# Supply.net
KiCad netlist of a schematic drawn in Altium Designer
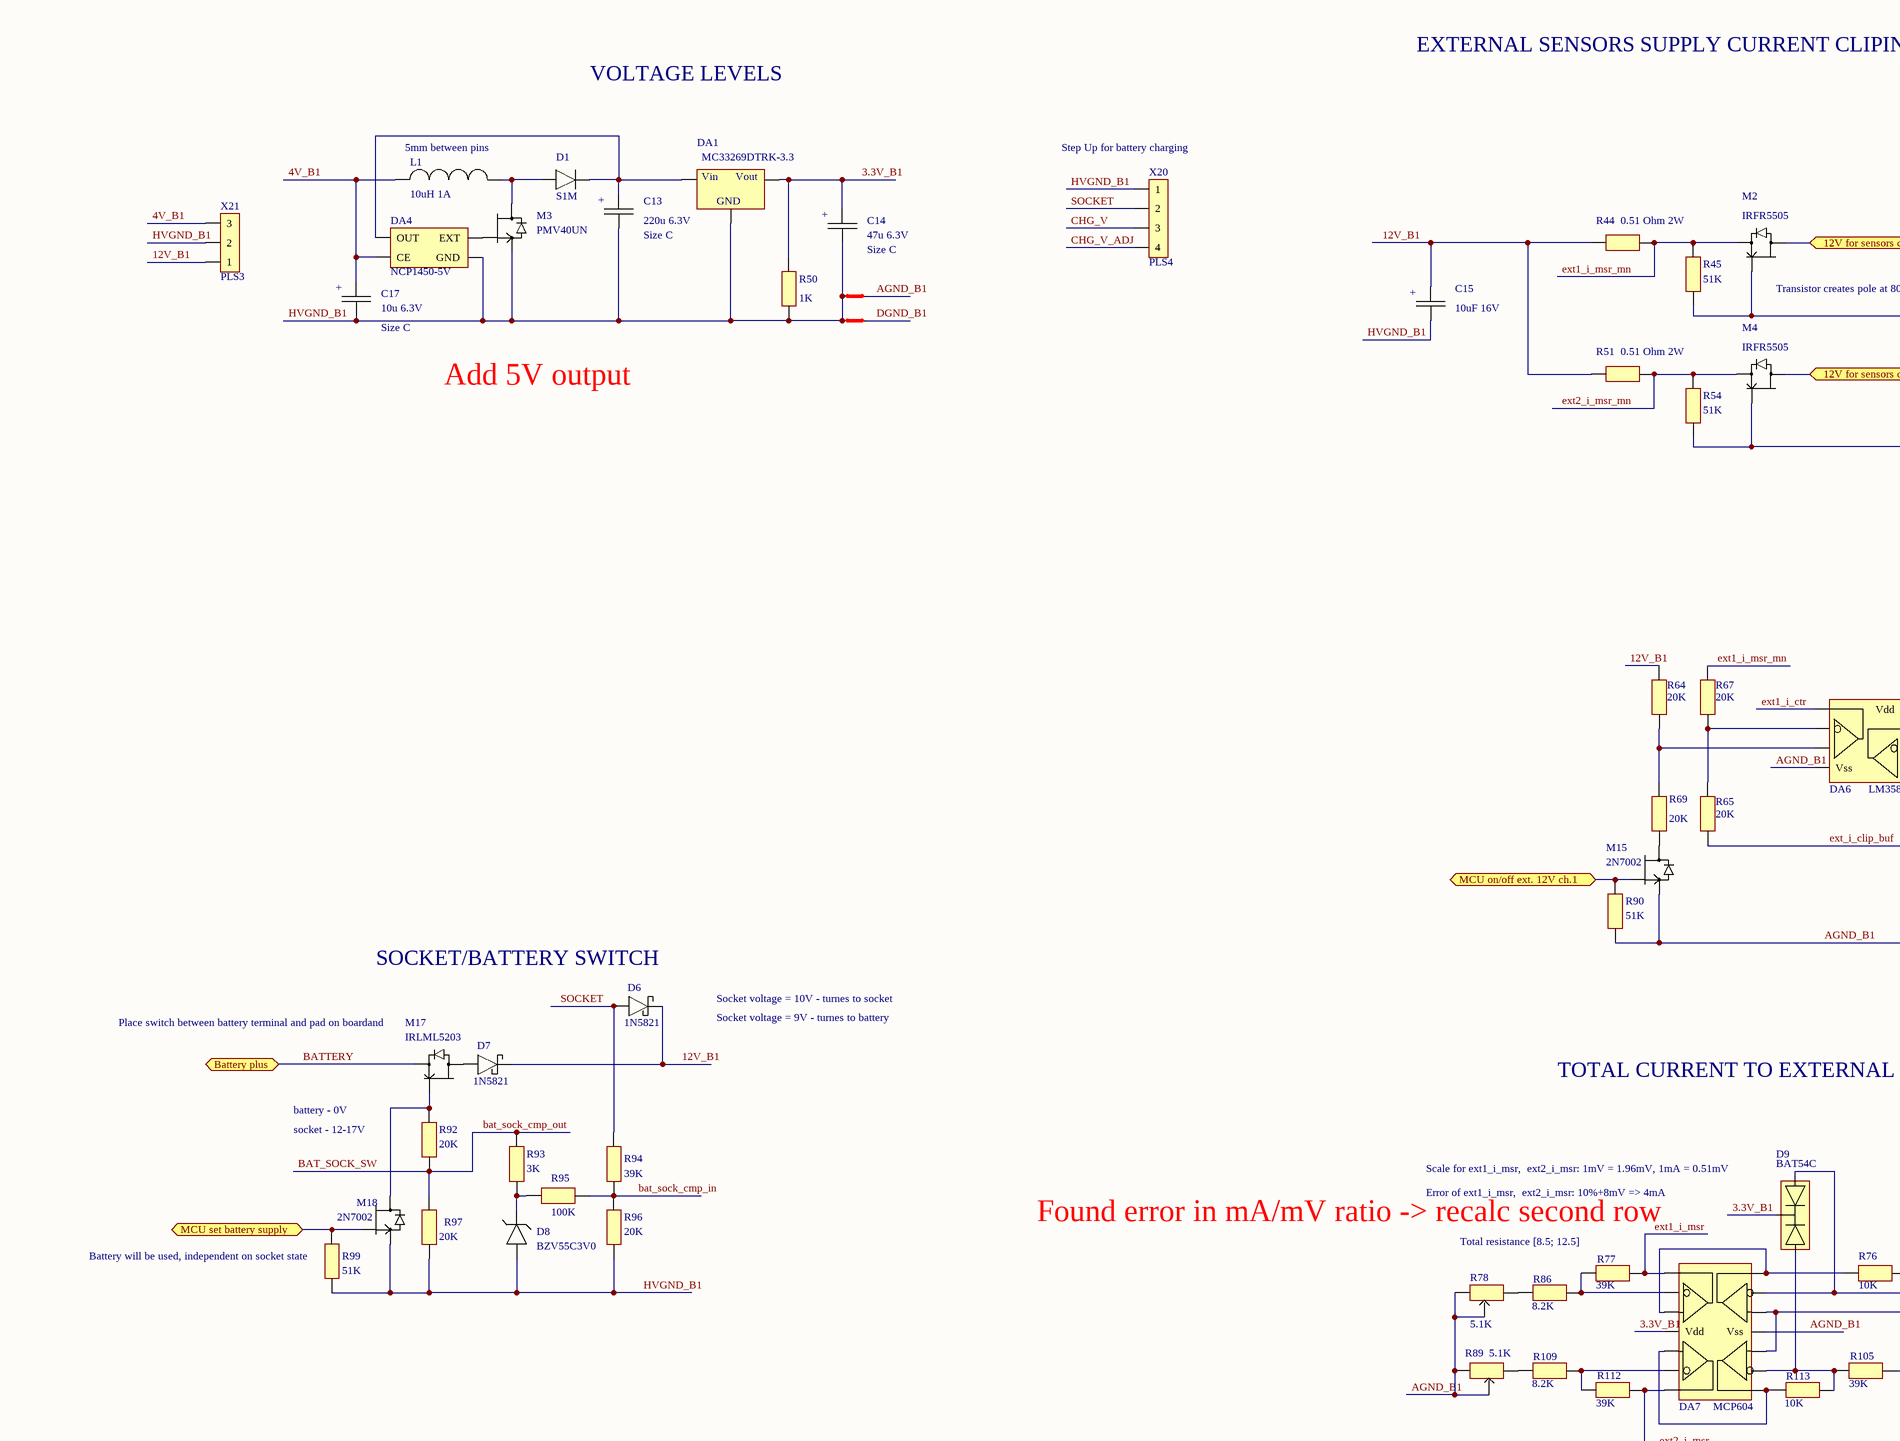
[diagram p0: Supply.SchDoc, top left]
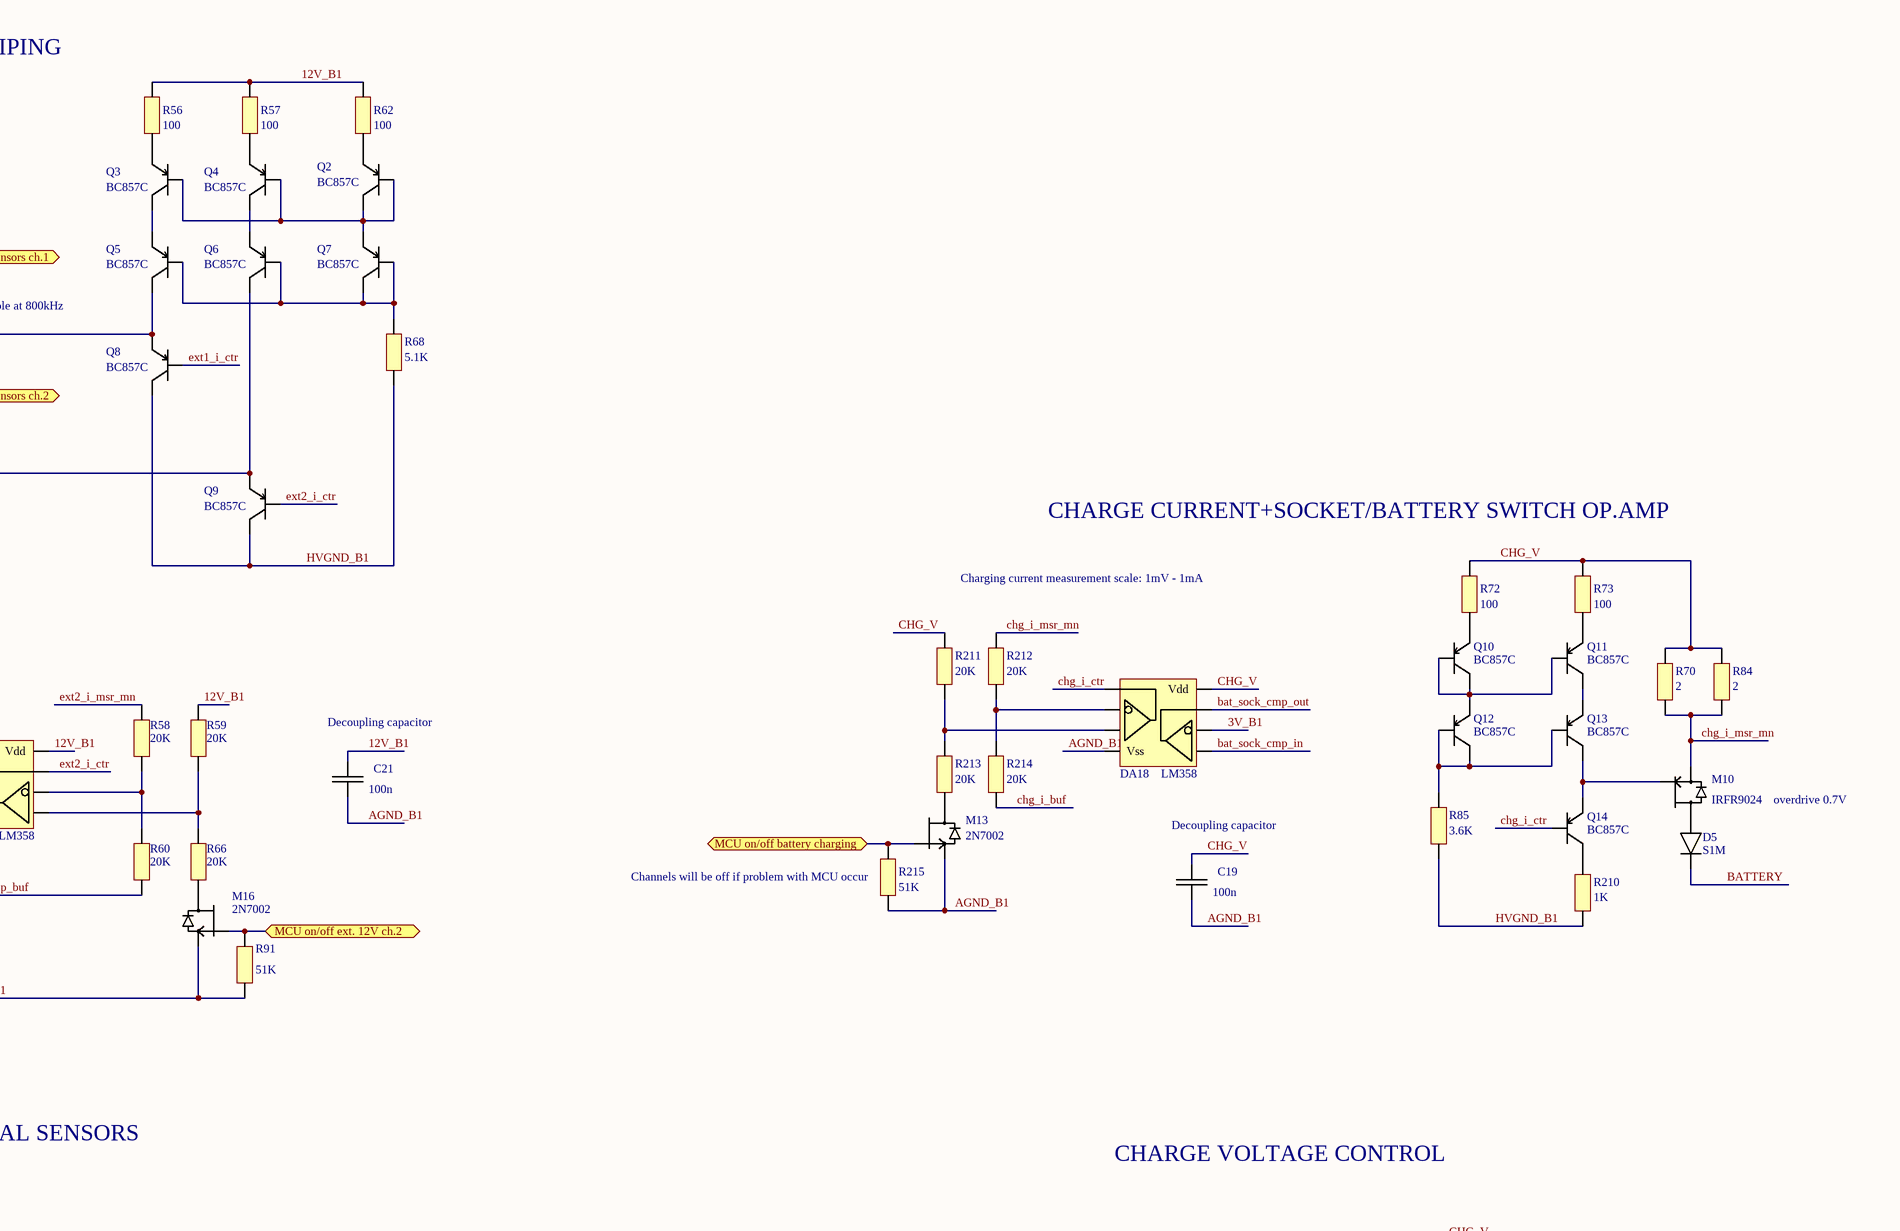
[diagram p1: Supply.SchDoc, top right]
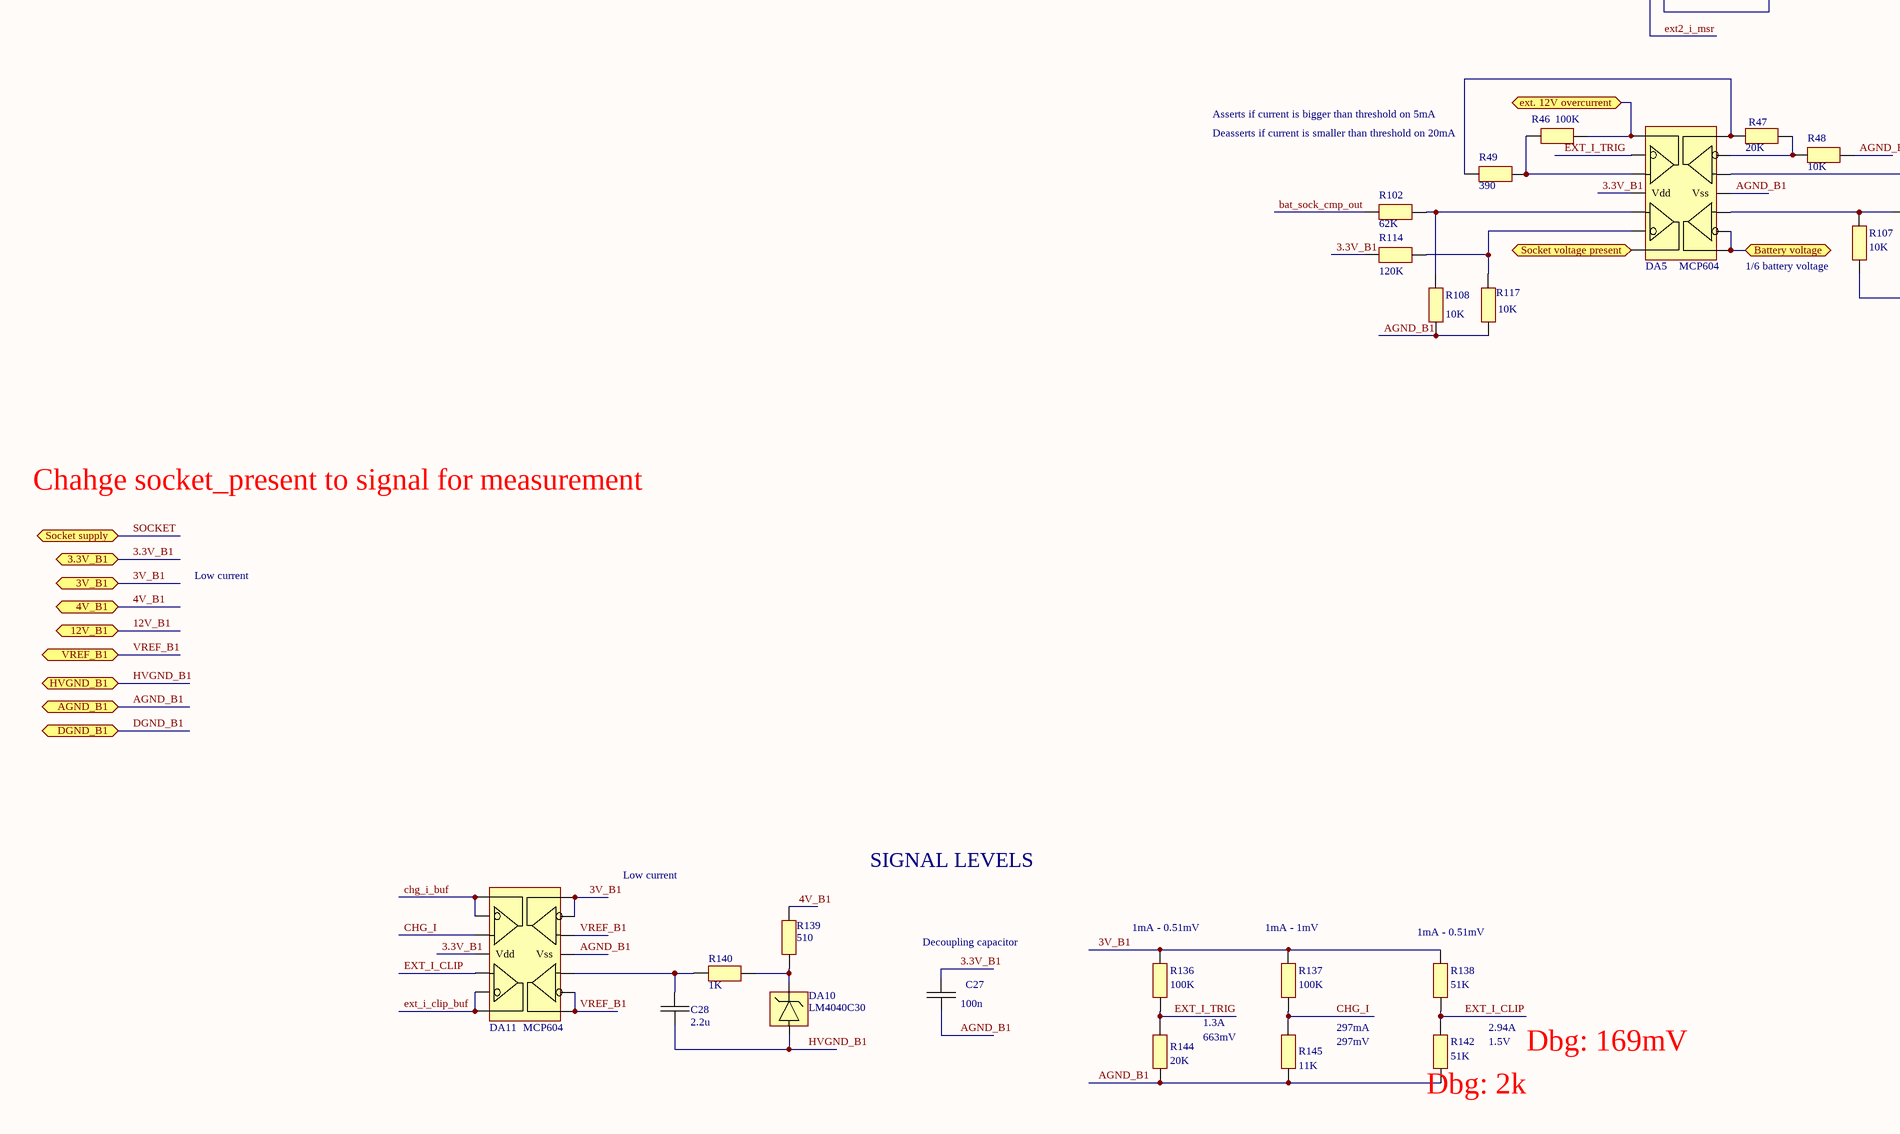
[diagram p2: Supply.SchDoc, bottom left]
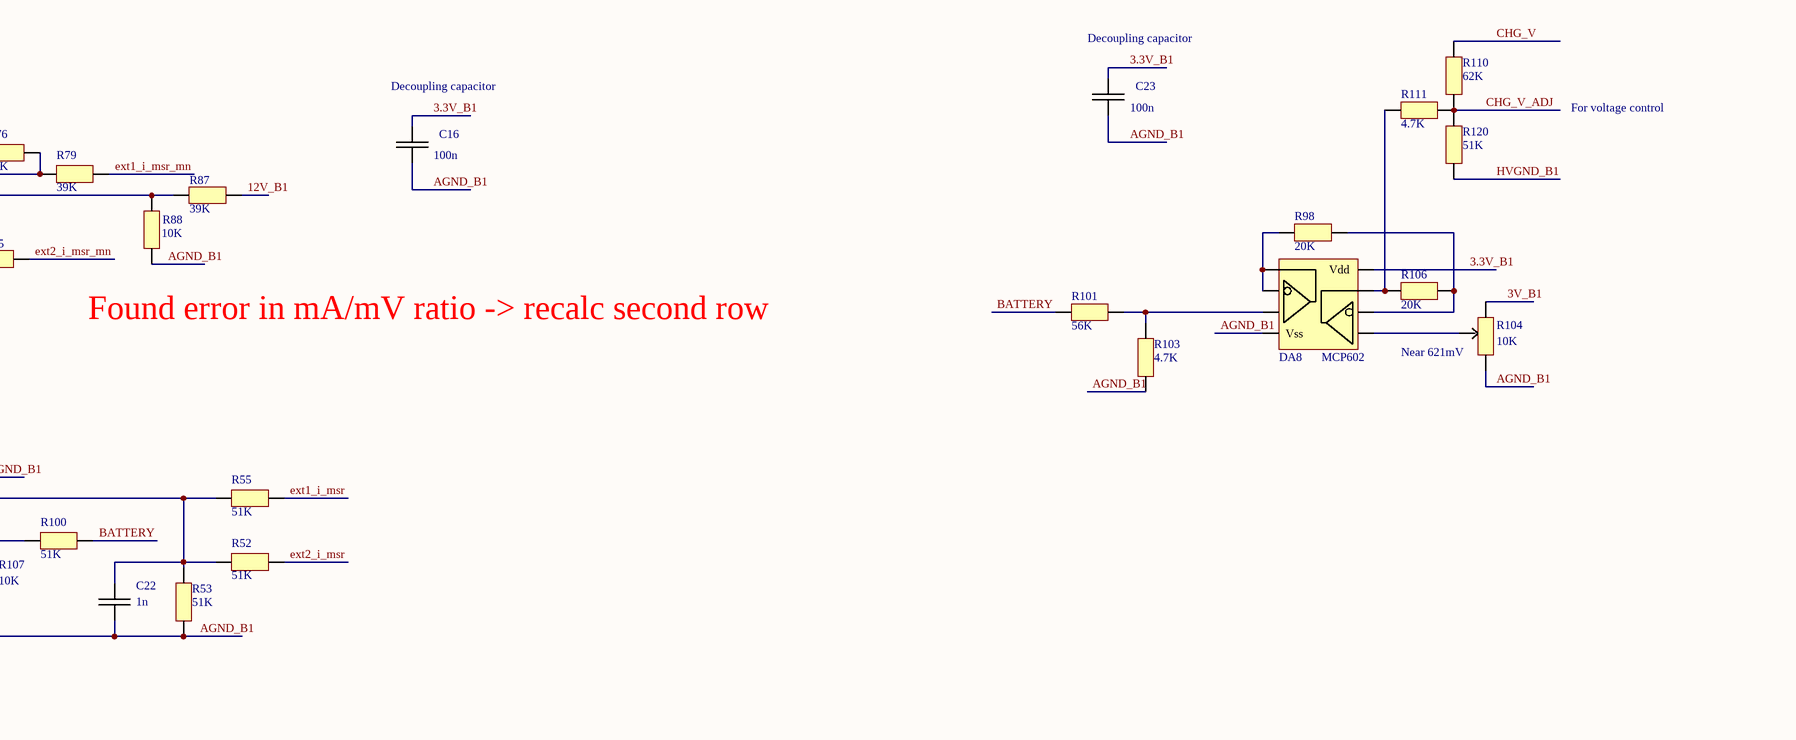
[diagram p3: Supply.SchDoc, bottom right]

(export (version "E")
  (design (tool "Eeschema 10.0.6"))
  (components
    (comp (ref "C13")
      (value "220u 6.3V")
      (footprint "CALUM_SMD_C")
      (libsource (lib "PRIM_fact") (part "C_POL"))
    )
    (comp (ref "C14")
      (value "47u 6.3V")
      (footprint "CALUM_SMD_C")
      (libsource (lib "PRIM_fact") (part "C_POL"))
    )
    (comp (ref "C15")
      (value "10uF 16V")
      (footprint "CALUM_THT_E5D13")
      (libsource (lib "PRIM_fact") (part "C_POL"))
    )
    (comp (ref "C16") (value "100n") (footprint "0805") (libsource (lib "PRIM_fact") (part "C")))
    (comp (ref "C17")
      (value "10u 6.3V")
      (footprint "CALUM_SMD_C")
      (libsource (lib "PRIM_fact") (part "C_POL"))
    )
    (comp (ref "C19") (value "100n") (footprint "0805") (libsource (lib "PRIM_fact") (part "C")))
    (comp (ref "C21") (value "100n") (footprint "0805") (libsource (lib "PRIM_fact") (part "C")))
    (comp (ref "C22") (value "1n") (footprint "0805") (libsource (lib "PRIM_fact") (part "C")))
    (comp (ref "C23") (value "100n") (footprint "0805") (libsource (lib "PRIM_fact") (part "C")))
    (comp (ref "C27") (value "100n") (footprint "0805") (libsource (lib "PRIM_fact") (part "C")))
    (comp (ref "C28") (value "2.2u") (footprint "0805") (libsource (lib "PRIM_fact") (part "C")))
    (comp (ref "D1") (value "S1M") (footprint "DO-214AC") (libsource (lib "PRIM_fact") (part "D")))
    (comp (ref "D5") (value "S1M") (footprint "DO-214AC") (libsource (lib "PRIM_fact") (part "D")))
    (comp (ref "D6") (value "1N5821") (footprint "DO-201AD") (libsource (lib "PRIM_fact") (part "D_Shottky")))
    (comp (ref "D7") (value "1N5821") (footprint "DO-201AD") (libsource (lib "PRIM_fact") (part "D_Shottky")))
    (comp (ref "D8")
      (value "BZV55C3V0")
      (footprint "SOD80")
      (libsource (lib "PRIM_fact") (part "Zener diode"))
    )
    (comp (ref "D9") (value "BAT54C") (footprint "SOT-23") (libsource (lib "PRIM_fact") (part "2xD2")))
    (comp (ref "DA1")
      (value "MC33269DTRK-3.3")
      (footprint "LINREG_DPAK")
      (libsource (lib "IC_fact") (part "LINEAR_REGULATOR"))
    )
    (comp (ref "DA4") (value "NCP1450-5V") (footprint "TSSOP5") (libsource (lib "IC_fact") (part "ncp1450")))
    (comp (ref "DA5") (value "MCP604") (footprint "SOP14") (libsource (lib "IC_fact") (part "4xOP.AMP")))
    (comp (ref "DA6") (value "LM358") (footprint "SOP8") (libsource (lib "IC_fact") (part "2xOP.AMP")))
    (comp (ref "DA7") (value "MCP604") (footprint "SOP14") (libsource (lib "IC_fact") (part "4xOP.AMP")))
    (comp (ref "DA8") (value "MCP602") (footprint "SOP8") (libsource (lib "IC_fact") (part "2xOP.AMP")))
    (comp (ref "DA10")
      (value "LM4040C30")
      (footprint "SOT-23")
      (libsource (lib "PRIM_fact") (part "Shunt_VREF"))
    )
    (comp (ref "DA11") (value "MCP604") (footprint "SOP14") (libsource (lib "IC_fact") (part "4xOP.AMP")))
    (comp (ref "DA18") (value "LM358") (footprint "SOP8") (libsource (lib "IC_fact") (part "2xOP.AMP")))
    (comp (ref "L1")
      (value "10uH 1A")
      (footprint "INDUCTOR_5mm")
      (libsource (lib "PRIM_fact") (part "Inductor"))
    )
    (comp (ref "M2")
      (value "IRFR5505")
      (footprint "TO-252(DPAK)")
      (libsource (lib "PRIM_fact") (part "PMOS+DIODE"))
    )
    (comp (ref "M3") (value "PMV40UN") (footprint "SOT-23") (libsource (lib "PRIM_fact") (part "NMOS+DIODE")))
    (comp (ref "M4")
      (value "IRFR5505")
      (footprint "TO-252(DPAK)")
      (libsource (lib "PRIM_fact") (part "PMOS+DIODE"))
    )
    (comp (ref "M10")
      (value "IRFR9024")
      (footprint "TO-252(DPAK)")
      (libsource (lib "PRIM_fact") (part "PMOS+DIODE"))
    )
    (comp (ref "M13") (value "2N7002") (footprint "SOT-23") (libsource (lib "PRIM_fact") (part "NMOS+DIODE")))
    (comp (ref "M15") (value "2N7002") (footprint "SOT-23") (libsource (lib "PRIM_fact") (part "NMOS+DIODE")))
    (comp (ref "M16") (value "2N7002") (footprint "SOT-23") (libsource (lib "PRIM_fact") (part "NMOS+DIODE")))
    (comp (ref "M17")
      (value "IRLML5203")
      (footprint "SOT-23")
      (libsource (lib "PRIM_fact") (part "PMOS+DIODE"))
    )
    (comp (ref "M18") (value "2N7002") (footprint "SOT-23") (libsource (lib "PRIM_fact") (part "NMOS+DIODE")))
    (comp (ref "N1") (value "NetTie") (footprint "NET_TIE_1mm") (libsource (lib "PRIM_fact") (part "NetTie")))
    (comp (ref "N2") (value "NetTie") (footprint "NET_TIE_1mm") (libsource (lib "PRIM_fact") (part "NetTie")))
    (comp (ref "Q2") (value "BC857C") (footprint "SOT-23") (libsource (lib "PRIM_fact") (part "PNP")))
    (comp (ref "Q3") (value "BC857C") (footprint "SOT-23") (libsource (lib "PRIM_fact") (part "PNP")))
    (comp (ref "Q4") (value "BC857C") (footprint "SOT-23") (libsource (lib "PRIM_fact") (part "PNP")))
    (comp (ref "Q5") (value "BC857C") (footprint "SOT-23") (libsource (lib "PRIM_fact") (part "PNP")))
    (comp (ref "Q6") (value "BC857C") (footprint "SOT-23") (libsource (lib "PRIM_fact") (part "PNP")))
    (comp (ref "Q7") (value "BC857C") (footprint "SOT-23") (libsource (lib "PRIM_fact") (part "PNP")))
    (comp (ref "Q8") (value "BC857C") (footprint "SOT-23") (libsource (lib "PRIM_fact") (part "PNP")))
    (comp (ref "Q9") (value "BC857C") (footprint "SOT-23") (libsource (lib "PRIM_fact") (part "PNP")))
    (comp (ref "Q10") (value "BC857C") (footprint "SOT-23") (libsource (lib "PRIM_fact") (part "PNP")))
    (comp (ref "Q11") (value "BC857C") (footprint "SOT-23") (libsource (lib "PRIM_fact") (part "PNP")))
    (comp (ref "Q12") (value "BC857C") (footprint "SOT-23") (libsource (lib "PRIM_fact") (part "PNP")))
    (comp (ref "Q13") (value "BC857C") (footprint "SOT-23") (libsource (lib "PRIM_fact") (part "PNP")))
    (comp (ref "Q14") (value "BC857C") (footprint "SOT-23") (libsource (lib "PRIM_fact") (part "PNP")))
    (comp (ref "R44") (value "0.51 Ohm 2W") (footprint "RES_2W") (libsource (lib "PRIM_fact") (part "R")))
    (comp (ref "R45") (value "51K") (footprint "0805") (libsource (lib "") (part "R_1")))
    (comp (ref "R46") (value "100K") (footprint "0805") (libsource (lib "PRIM_fact") (part "R")))
    (comp (ref "R47") (value "20K") (footprint "0805") (libsource (lib "PRIM_fact") (part "R")))
    (comp (ref "R48") (value "10K") (footprint "0805") (libsource (lib "PRIM_fact") (part "R")))
    (comp (ref "R49") (value "390") (footprint "0805") (libsource (lib "PRIM_fact") (part "R")))
    (comp (ref "R50") (value "1K") (footprint "0805") (libsource (lib "") (part "R_1")))
    (comp (ref "R51") (value "0.51 Ohm 2W") (footprint "RES_2W") (libsource (lib "PRIM_fact") (part "R")))
    (comp (ref "R52") (value "51K") (footprint "0805") (libsource (lib "PRIM_fact") (part "R")))
    (comp (ref "R53") (value "51K") (footprint "0805") (libsource (lib "") (part "R_3")))
    (comp (ref "R54") (value "51K") (footprint "0805") (libsource (lib "") (part "R_1")))
    (comp (ref "R55") (value "51K") (footprint "0805") (libsource (lib "PRIM_fact") (part "R")))
    (comp (ref "R56") (value "100") (footprint "0805") (libsource (lib "") (part "R_1")))
    (comp (ref "R57") (value "100") (footprint "0805") (libsource (lib "") (part "R_1")))
    (comp (ref "R58") (value "20K") (footprint "0805") (libsource (lib "") (part "R_2")))
    (comp (ref "R59") (value "20K") (footprint "0805") (libsource (lib "") (part "R_2")))
    (comp (ref "R60") (value "20K") (footprint "0805") (libsource (lib "") (part "R_1")))
    (comp (ref "R62") (value "100") (footprint "0805") (libsource (lib "") (part "R_1")))
    (comp (ref "R64") (value "20K") (footprint "0805") (libsource (lib "") (part "R_3")))
    (comp (ref "R65") (value "20K") (footprint "0805") (libsource (lib "") (part "R_2")))
    (comp (ref "R66") (value "20K") (footprint "0805") (libsource (lib "") (part "R_1")))
    (comp (ref "R67") (value "20K") (footprint "0805") (libsource (lib "") (part "R_2")))
    (comp (ref "R68") (value "5.1K") (footprint "0805") (libsource (lib "") (part "R_1")))
    (comp (ref "R69") (value "20K") (footprint "0805") (libsource (lib "") (part "R_1")))
    (comp (ref "R70") (value "2") (footprint "1206") (libsource (lib "") (part "R_1")))
    (comp (ref "R72") (value "100") (footprint "0805") (libsource (lib "") (part "R_1")))
    (comp (ref "R73") (value "100") (footprint "0805") (libsource (lib "") (part "R_1")))
    (comp (ref "R76") (value "10K") (footprint "0805") (libsource (lib "PRIM_fact") (part "R")))
    (comp (ref "R77") (value "39K") (footprint "0805") (libsource (lib "") (part "R_2")))
    (comp (ref "R78") (value "5.1K") (footprint "3305SMD(adj res)") (libsource (lib "") (part "Radj_1")))
    (comp (ref "R79") (value "39K") (footprint "0805") (libsource (lib "PRIM_fact") (part "R")))
    (comp (ref "R84") (value "2") (footprint "1206") (libsource (lib "") (part "R_1")))
    (comp (ref "R85") (value "3.6K") (footprint "0805") (libsource (lib "") (part "R_1")))
    (comp (ref "R86") (value "8.2K") (footprint "0805") (libsource (lib "") (part "R_2")))
    (comp (ref "R87") (value "39K") (footprint "0805") (libsource (lib "PRIM_fact") (part "R")))
    (comp (ref "R88") (value "10K") (footprint "0805") (libsource (lib "") (part "R_1")))
    (comp (ref "R89")
      (value "5.1K")
      (footprint "3305SMD(adj res)")
      (libsource (lib "PRIM_fact") (part "Radj"))
    )
    (comp (ref "R90") (value "51K") (footprint "0805") (libsource (lib "") (part "R_1")))
    (comp (ref "R91") (value "51K") (footprint "0805") (libsource (lib "") (part "R_1")))
    (comp (ref "R92") (value "20K") (footprint "0805") (libsource (lib "") (part "R_1")))
    (comp (ref "R93") (value "3K") (footprint "0805") (libsource (lib "PRIM_fact") (part "R")))
    (comp (ref "R94") (value "39K") (footprint "0805") (libsource (lib "PRIM_fact") (part "R")))
    (comp (ref "R95") (value "100K") (footprint "0805") (libsource (lib "") (part "R_3")))
    (comp (ref "R96") (value "20K") (footprint "0805") (libsource (lib "PRIM_fact") (part "R")))
    (comp (ref "R97") (value "20K") (footprint "0805") (libsource (lib "") (part "R_1")))
    (comp (ref "R98") (value "20K") (footprint "0805") (libsource (lib "") (part "R_2")))
    (comp (ref "R99") (value "51K") (footprint "0805") (libsource (lib "PRIM_fact") (part "R")))
    (comp (ref "R100") (value "51K") (footprint "0805") (libsource (lib "") (part "R_2")))
    (comp (ref "R101") (value "56K") (footprint "0805") (libsource (lib "") (part "R_1")))
    (comp (ref "R102") (value "62K") (footprint "0805") (libsource (lib "") (part "R_2")))
    (comp (ref "R103") (value "4.7K") (footprint "0805") (libsource (lib "PRIM_fact") (part "R")))
    (comp (ref "R104")
      (value "10K")
      (footprint "3296 X W(ADJ RES)")
      (libsource (lib "PRIM_fact") (part "Radj"))
    )
    (comp (ref "R105") (value "39K") (footprint "0805") (libsource (lib "") (part "R_2")))
    (comp (ref "R106") (value "20K") (footprint "0805") (libsource (lib "") (part "R_3")))
    (comp (ref "R107") (value "10K") (footprint "0805") (libsource (lib "") (part "R_3")))
    (comp (ref "R108") (value "10K") (footprint "0805") (libsource (lib "") (part "R_1")))
    (comp (ref "R109") (value "8.2K") (footprint "0805") (libsource (lib "") (part "R_2")))
    (comp (ref "R110") (value "62K") (footprint "0805") (libsource (lib "") (part "R_1")))
    (comp (ref "R111") (value "4.7K") (footprint "0805") (libsource (lib "") (part "R_2")))
    (comp (ref "R112") (value "39K") (footprint "0805") (libsource (lib "") (part "R_2")))
    (comp (ref "R113") (value "10K") (footprint "0805") (libsource (lib "") (part "R_2")))
    (comp (ref "R114") (value "120K") (footprint "0805") (libsource (lib "PRIM_fact") (part "R")))
    (comp (ref "R117") (value "10K") (footprint "0805") (libsource (lib "") (part "R_1")))
    (comp (ref "R120") (value "51K") (footprint "0805") (libsource (lib "") (part "R_1")))
    (comp (ref "R136") (value "100K") (footprint "0805") (libsource (lib "") (part "R_1")))
    (comp (ref "R137") (value "100K") (footprint "0805") (libsource (lib "") (part "R_1")))
    (comp (ref "R138") (value "51K") (footprint "0805") (libsource (lib "") (part "R_1")))
    (comp (ref "R139") (value "510") (footprint "0805") (libsource (lib "PRIM_fact") (part "R")))
    (comp (ref "R140") (value "1K") (footprint "0805") (libsource (lib "") (part "R_3")))
    (comp (ref "R142") (value "51K") (footprint "0805") (libsource (lib "") (part "R_1")))
    (comp (ref "R144") (value "20K") (footprint "0805") (libsource (lib "") (part "R_1")))
    (comp (ref "R145") (value "11K") (footprint "0805") (libsource (lib "") (part "R_1")))
    (comp (ref "R210") (value "1K") (footprint "0805") (libsource (lib "") (part "R_1")))
    (comp (ref "R211") (value "20K") (footprint "0805") (libsource (lib "") (part "R_1")))
    (comp (ref "R212") (value "20K") (footprint "0805") (libsource (lib "") (part "R_1")))
    (comp (ref "R213") (value "20K") (footprint "0805") (libsource (lib "") (part "R_1")))
    (comp (ref "R214") (value "20K") (footprint "0805") (libsource (lib "") (part "R_1")))
    (comp (ref "R215") (value "51K") (footprint "0805") (libsource (lib "") (part "R_1")))
    (comp (ref "X20") (value "PLS4") (footprint "PLS_4_BIG") (libsource (lib "PRIM_fact") (part "CONT_4")))
    (comp (ref "X21") (value "PLS3") (footprint "PLS_3_BIG") (libsource (lib "PRIM_fact") (part "CONT_3")))
  )
  (nets
    (net (code "1") (name "/3.3V_B1") (class "Default")
      (node (ref "C14") (pin "1") (pintype "passive"))
      (node (ref "C16") (pin "2") (pintype "passive"))
      (node (ref "C23") (pin "2") (pintype "passive"))
      (node (ref "C27") (pin "2") (pintype "passive"))
      (node (ref "D9") (pin "3") (pinfunction "AK_3") (pintype "passive"))
      (node (ref "DA1") (pin "out") (pinfunction "Vout_out") (pintype "passive"))
      (node (ref "DA11") (pin "4") (pinfunction "Vdd_4") (pintype "passive"))
      (node (ref "DA5") (pin "4") (pinfunction "Vdd_4") (pintype "passive"))
      (node (ref "DA7") (pin "4") (pinfunction "Vdd_4") (pintype "passive"))
      (node (ref "DA8") (pin "8") (pinfunction "Vdd_8") (pintype "passive"))
      (node (ref "R114") (pin "2") (pintype "passive"))
      (node (ref "R50") (pin "1") (pintype "passive"))
    )
    (net (code "2") (name "/3V_B1") (class "Default")
      (node (ref "DA11") (pin "13") (pintype "passive"))
      (node (ref "DA11") (pin "14") (pintype "passive"))
      (node (ref "DA18") (pin "6") (pintype "passive"))
      (node (ref "R104") (pin "1") (pintype "passive"))
      (node (ref "R136") (pin "1") (pintype "passive"))
      (node (ref "R137") (pin "1") (pintype "passive"))
      (node (ref "R138") (pin "1") (pintype "passive"))
    )
    (net (code "3") (name "/4V_B1") (class "Default")
      (node (ref "C17") (pin "1") (pintype "passive"))
      (node (ref "DA4") (pin "1") (pinfunction "CE_1") (pintype "passive"))
      (node (ref "L1") (pin "2") (pintype "passive"))
      (node (ref "R139") (pin "1") (pintype "passive"))
      (node (ref "X21") (pin "3") (pinfunction "3_3") (pintype "passive"))
    )
    (net (code "4") (name "/12V for sensors ch.1") (class "Default")
      (node (ref "M2") (pin "3") (pintype "passive"))
    )
    (net (code "5") (name "/12V for sensors ch.2") (class "Default")
      (node (ref "M4") (pin "3") (pintype "passive"))
    )
    (net (code "6") (name "/12V_B1") (class "Default")
      (node (ref "C15") (pin "1") (pintype "passive"))
      (node (ref "C21") (pin "2") (pintype "passive"))
      (node (ref "D6") (pin "2") (pintype "passive"))
      (node (ref "D7") (pin "2") (pintype "passive"))
      (node (ref "DA6") (pin "8") (pinfunction "Vdd_8") (pintype "passive"))
      (node (ref "R44") (pin "2") (pintype "passive"))
      (node (ref "R51") (pin "2") (pintype "passive"))
      (node (ref "R56") (pin "1") (pintype "passive"))
      (node (ref "R57") (pin "1") (pintype "passive"))
      (node (ref "R59") (pin "2") (pintype "passive"))
      (node (ref "R62") (pin "1") (pintype "passive"))
      (node (ref "R64") (pin "2") (pintype "passive"))
      (node (ref "R87") (pin "1") (pintype "passive"))
      (node (ref "X21") (pin "1") (pinfunction "1_1") (pintype "passive"))
    )
    (net (code "7") (name "/AGND_B1") (class "Default")
      (node (ref "C16") (pin "1") (pintype "passive"))
      (node (ref "C19") (pin "1") (pintype "passive"))
      (node (ref "C21") (pin "1") (pintype "passive"))
      (node (ref "C22") (pin "1") (pintype "passive"))
      (node (ref "C23") (pin "1") (pintype "passive"))
      (node (ref "C27") (pin "1") (pintype "passive"))
      (node (ref "DA11") (pin "11") (pinfunction "Vss_11") (pintype "passive"))
      (node (ref "DA18") (pin "4") (pinfunction "Vss_4") (pintype "passive"))
      (node (ref "DA5") (pin "11") (pinfunction "Vss_11") (pintype "passive"))
      (node (ref "DA6") (pin "4") (pinfunction "Vss_4") (pintype "passive"))
      (node (ref "DA7") (pin "11") (pinfunction "Vss_11") (pintype "passive"))
      (node (ref "DA8") (pin "4") (pinfunction "Vss_4") (pintype "passive"))
      (node (ref "M13") (pin "2") (pintype "passive"))
      (node (ref "M15") (pin "2") (pintype "passive"))
      (node (ref "M16") (pin "2") (pintype "passive"))
      (node (ref "N1") (pin "2") (pintype "passive"))
      (node (ref "R103") (pin "2") (pintype "passive"))
      (node (ref "R104") (pin "2") (pintype "passive"))
      (node (ref "R107") (pin "1") (pintype "passive"))
      (node (ref "R108") (pin "2") (pintype "passive"))
      (node (ref "R117") (pin "2") (pintype "passive"))
      (node (ref "R142") (pin "2") (pintype "passive"))
      (node (ref "R144") (pin "2") (pintype "passive"))
      (node (ref "R145") (pin "2") (pintype "passive"))
      (node (ref "R215") (pin "2") (pintype "passive"))
      (node (ref "R48") (pin "1") (pintype "passive"))
      (node (ref "R53") (pin "1") (pintype "passive"))
      (node (ref "R78") (pin "1") (pintype "passive"))
      (node (ref "R78") (pin "3") (pintype "passive"))
      (node (ref "R88") (pin "2") (pintype "passive"))
      (node (ref "R89") (pin "2") (pintype "passive"))
      (node (ref "R89") (pin "3") (pintype "passive"))
      (node (ref "R90") (pin "2") (pintype "passive"))
      (node (ref "R91") (pin "2") (pintype "passive"))
    )
    (net (code "8") (name "/BATTERY") (class "Default")
      (node (ref "D5") (pin "2") (pintype "passive"))
      (node (ref "M17") (pin "2") (pintype "passive"))
      (node (ref "R100") (pin "2") (pintype "passive"))
      (node (ref "R101") (pin "2") (pintype "passive"))
    )
    (net (code "9") (name "/BAT_SOCK_SW") (class "Default")
      (node (ref "DA18") (pin "7") (pintype "passive"))
      (node (ref "R102") (pin "1") (pintype "passive"))
      (node (ref "R92") (pin "2") (pintype "passive"))
      (node (ref "R93") (pin "1") (pintype "passive"))
      (node (ref "R97") (pin "1") (pintype "passive"))
    )
    (net (code "10") (name "/Battery voltage") (class "Default")
      (node (ref "DA5") (pin "8") (pintype "passive"))
      (node (ref "DA5") (pin "9") (pintype "passive"))
    )
    (net (code "11") (name "/CHG_I") (class "Default")
      (node (ref "DA11") (pin "3") (pintype "passive"))
      (node (ref "R137") (pin "2") (pintype "passive"))
      (node (ref "R145") (pin "1") (pintype "passive"))
    )
    (net (code "12") (name "/CHG_V") (class "Default")
      (node (ref "C19") (pin "2") (pintype "passive"))
      (node (ref "DA18") (pin "8") (pinfunction "Vdd_8") (pintype "passive"))
      (node (ref "R110") (pin "1") (pintype "passive"))
      (node (ref "R211") (pin "1") (pintype "passive"))
      (node (ref "R70") (pin "1") (pintype "passive"))
      (node (ref "R72") (pin "1") (pintype "passive"))
      (node (ref "R73") (pin "1") (pintype "passive"))
      (node (ref "R84") (pin "1") (pintype "passive"))
      (node (ref "X20") (pin "3") (pinfunction "3_3") (pintype "passive"))
    )
    (net (code "13") (name "/CHG_V_ADJ") (class "Default")
      (node (ref "R110") (pin "2") (pintype "passive"))
      (node (ref "R111") (pin "2") (pintype "passive"))
      (node (ref "R120") (pin "1") (pintype "passive"))
      (node (ref "X20") (pin "4") (pinfunction "4_4") (pintype "passive"))
    )
    (net (code "14") (name "/DGND_B1") (class "Default") (node (ref "N2") (pin "2") (pintype "passive")))
    (net (code "15") (name "/EXT_I_CLIP") (class "Default")
      (node (ref "DA11") (pin "5") (pintype "passive"))
      (node (ref "R138") (pin "2") (pintype "passive"))
      (node (ref "R142") (pin "1") (pintype "passive"))
    )
    (net (code "16") (name "/EXT_I_TRIG") (class "Default")
      (node (ref "DA5") (pin "2") (pintype "passive"))
      (node (ref "R136") (pin "2") (pintype "passive"))
      (node (ref "R144") (pin "1") (pintype "passive"))
    )
    (net (code "17") (name "/HVGND_B1") (class "Default")
      (node (ref "C13") (pin "2") (pintype "passive"))
      (node (ref "C14") (pin "2") (pintype "passive"))
      (node (ref "C15") (pin "2") (pintype "passive"))
      (node (ref "C17") (pin "2") (pintype "passive"))
      (node (ref "C28") (pin "1") (pintype "passive"))
      (node (ref "D8") (pin "1") (pinfunction "A_1") (pintype "passive"))
      (node (ref "DA1") (pin "gnd") (pinfunction "GND_gnd") (pintype "passive"))
      (node (ref "DA10") (pin "2") (pinfunction "A_2") (pintype "passive"))
      (node (ref "DA4") (pin "4") (pinfunction "GND_4") (pintype "passive"))
      (node (ref "M18") (pin "2") (pintype "passive"))
      (node (ref "M3") (pin "2") (pintype "passive"))
      (node (ref "N1") (pin "1") (pintype "passive"))
      (node (ref "N2") (pin "1") (pintype "passive"))
      (node (ref "Q8") (pin "3") (pinfunction "C_3") (pintype "passive"))
      (node (ref "Q9") (pin "3") (pinfunction "C_3") (pintype "passive"))
      (node (ref "R120") (pin "2") (pintype "passive"))
      (node (ref "R210") (pin "2") (pintype "passive"))
      (node (ref "R50") (pin "2") (pintype "passive"))
      (node (ref "R68") (pin "2") (pintype "passive"))
      (node (ref "R85") (pin "2") (pintype "passive"))
      (node (ref "R96") (pin "2") (pintype "passive"))
      (node (ref "R97") (pin "2") (pintype "passive"))
      (node (ref "R99") (pin "2") (pintype "passive"))
      (node (ref "X20") (pin "1") (pinfunction "1_1") (pintype "passive"))
      (node (ref "X21") (pin "2") (pinfunction "2_2") (pintype "passive"))
    )
    (net (code "18") (name "/MCU on{slash}off battery charging") (class "Default")
      (node (ref "M13") (pin "1") (pintype "passive"))
      (node (ref "R215") (pin "1") (pintype "passive"))
    )
    (net (code "19") (name "/MCU on{slash}off ext. 12V ch.1") (class "Default")
      (node (ref "M15") (pin "1") (pintype "passive"))
      (node (ref "R90") (pin "1") (pintype "passive"))
    )
    (net (code "20") (name "/MCU on{slash}off ext. 12V ch.2") (class "Default")
      (node (ref "M16") (pin "1") (pintype "passive"))
      (node (ref "R91") (pin "1") (pintype "passive"))
    )
    (net (code "21") (name "/MCU set battery supply") (class "Default")
      (node (ref "M18") (pin "1") (pintype "passive"))
      (node (ref "R99") (pin "1") (pintype "passive"))
    )
    (net (code "22") (name "/SOCKET") (class "Default")
      (node (ref "D6") (pin "1") (pintype "passive"))
      (node (ref "R94") (pin "1") (pintype "passive"))
      (node (ref "X20") (pin "2") (pinfunction "2_2") (pintype "passive"))
    )
    (net (code "23") (name "/Socket voltage present") (class "Default")
      (node (ref "DA5") (pin "7") (pintype "passive"))
    )
    (net (code "24") (name "/VREF_B1") (class "Default")
      (node (ref "DA11") (pin "12") (pintype "passive"))
      (node (ref "DA11") (pin "8") (pintype "passive"))
      (node (ref "DA11") (pin "9") (pintype "passive"))
    )
    (net (code "25") (name "/bat_sock_cmp_in") (class "Default")
      (node (ref "DA18") (pin "5") (pintype "passive"))
      (node (ref "R94") (pin "2") (pintype "passive"))
      (node (ref "R95") (pin "2") (pintype "passive"))
      (node (ref "R96") (pin "1") (pintype "passive"))
    )
    (net (code "26") (name "/chg_i_buf") (class "Default")
      (node (ref "DA11") (pin "1") (pintype "passive"))
      (node (ref "DA11") (pin "2") (pintype "passive"))
      (node (ref "R214") (pin "2") (pintype "passive"))
    )
    (net (code "27") (name "/chg_i_ctr") (class "Default")
      (node (ref "DA18") (pin "1") (pintype "passive"))
      (node (ref "Q14") (pin "1") (pinfunction "B_1") (pintype "passive"))
    )
    (net (code "28") (name "/chg_i_msr_mn") (class "Default")
      (node (ref "M10") (pin "2") (pintype "passive"))
      (node (ref "R212") (pin "1") (pintype "passive"))
      (node (ref "R70") (pin "2") (pintype "passive"))
      (node (ref "R84") (pin "2") (pintype "passive"))
    )
    (net (code "29") (name "/ext. 12V overcurrent") (class "Default")
      (node (ref "DA5") (pin "1") (pintype "passive"))
      (node (ref "R46") (pin "1") (pintype "passive"))
    )
    (net (code "30") (name "/ext1_i_ctr") (class "Default")
      (node (ref "DA6") (pin "1") (pintype "passive"))
      (node (ref "Q8") (pin "1") (pinfunction "B_1") (pintype "passive"))
    )
    (net (code "31") (name "/ext1_i_msr") (class "Default")
      (node (ref "DA7") (pin "1") (pintype "passive"))
      (node (ref "R55") (pin "1") (pintype "passive"))
      (node (ref "R77") (pin "2") (pintype "passive"))
    )
    (net (code "32") (name "/ext1_i_msr_mn") (class "Default")
      (node (ref "M2") (pin "2") (pintype "passive"))
      (node (ref "R44") (pin "1") (pintype "passive"))
      (node (ref "R45") (pin "1") (pintype "passive"))
      (node (ref "R67") (pin "2") (pintype "passive"))
      (node (ref "R79") (pin "1") (pintype "passive"))
    )
    (net (code "33") (name "/ext2_i_ctr") (class "Default")
      (node (ref "DA6") (pin "7") (pintype "passive"))
      (node (ref "Q9") (pin "1") (pinfunction "B_1") (pintype "passive"))
    )
    (net (code "34") (name "/ext2_i_msr") (class "Default")
      (node (ref "DA7") (pin "7") (pintype "passive"))
      (node (ref "R112") (pin "2") (pintype "passive"))
      (node (ref "R52") (pin "1") (pintype "passive"))
    )
    (net (code "35") (name "/ext2_i_msr_mn") (class "Default")
      (node (ref "M4") (pin "2") (pintype "passive"))
      (node (ref "R105") (pin "2") (pintype "passive"))
      (node (ref "R51") (pin "1") (pintype "passive"))
      (node (ref "R54") (pin "1") (pintype "passive"))
      (node (ref "R58") (pin "2") (pintype "passive"))
    )
    (net (code "36") (name "/ext_i_clip_buf") (class "Default")
      (node (ref "DA11") (pin "6") (pintype "passive"))
      (node (ref "DA11") (pin "7") (pintype "passive"))
      (node (ref "R60") (pin "2") (pintype "passive"))
      (node (ref "R65") (pin "1") (pintype "passive"))
    )
    (net (code "37") (name "Net-(C22-Pad2)") (class "Default")
      (node (ref "C22") (pin "2") (pintype "passive"))
      (node (ref "DA5") (pin "12") (pintype "passive"))
      (node (ref "R52") (pin "2") (pintype "passive"))
      (node (ref "R53") (pin "2") (pintype "passive"))
      (node (ref "R55") (pin "2") (pintype "passive"))
    )
    (net (code "38") (name "Net-(C28-Pad2)") (class "Default")
      (node (ref "C28") (pin "2") (pintype "passive"))
      (node (ref "DA11") (pin "10") (pintype "passive"))
      (node (ref "R140") (pin "1") (pintype "passive"))
    )
    (net (code "39") (name "Net-(D1-Pad1)") (class "Default")
      (node (ref "D1") (pin "1") (pintype "passive"))
      (node (ref "L1") (pin "1") (pintype "passive"))
      (node (ref "M3") (pin "3") (pintype "passive"))
    )
    (net (code "40") (name "Net-(D5-Pad1)") (class "Default")
      (node (ref "D5") (pin "1") (pintype "passive"))
      (node (ref "M10") (pin "3") (pintype "passive"))
    )
    (net (code "41") (name "Net-(D7-Pad1)") (class "Default")
      (node (ref "D7") (pin "1") (pintype "passive"))
      (node (ref "M17") (pin "3") (pintype "passive"))
    )
    (net (code "42") (name "Net-(D8-K)") (class "Default")
      (node (ref "D8") (pin "2") (pinfunction "K_2") (pintype "passive"))
      (node (ref "R93") (pin "2") (pintype "passive"))
      (node (ref "R95") (pin "1") (pintype "passive"))
    )
    (net (code "43") (name "Net-(D9-A1)") (class "Default")
      (node (ref "D9") (pin "1") (pinfunction "A1_1") (pintype "passive"))
      (node (ref "DA7") (pin "13") (pintype "passive"))
      (node (ref "R76") (pin "1") (pintype "passive"))
      (node (ref "R79") (pin "2") (pintype "passive"))
    )
    (net (code "44") (name "Net-(D9-K2)") (class "Default")
      (node (ref "D9") (pin "2") (pinfunction "K2_2") (pintype "passive"))
      (node (ref "DA7") (pin "9") (pintype "passive"))
      (node (ref "R105") (pin "1") (pintype "passive"))
      (node (ref "R113") (pin "2") (pintype "passive"))
    )
    (net (code "45") (name "Net-(DA1-Vin)") (class "Default")
      (node (ref "C13") (pin "1") (pintype "passive"))
      (node (ref "D1") (pin "2") (pintype "passive"))
      (node (ref "DA1") (pin "in") (pinfunction "Vin_in") (pintype "passive"))
      (node (ref "DA4") (pin "2") (pinfunction "OUT_2") (pintype "passive"))
    )
    (net (code "46") (name "Net-(DA4-EXT)") (class "Default")
      (node (ref "DA4") (pin "5") (pinfunction "EXT_5") (pintype "passive"))
      (node (ref "M3") (pin "1") (pintype "passive"))
    )
    (net (code "47") (name "Net-(DA5-Pad3)") (class "Default")
      (node (ref "DA5") (pin "3") (pintype "passive"))
      (node (ref "R46") (pin "2") (pintype "passive"))
      (node (ref "R49") (pin "1") (pintype "passive"))
    )
    (net (code "48") (name "Net-(DA5-Pad5)") (class "Default")
      (node (ref "DA5") (pin "5") (pintype "passive"))
      (node (ref "R102") (pin "2") (pintype "passive"))
      (node (ref "R108") (pin "1") (pintype "passive"))
    )
    (net (code "49") (name "Net-(DA5-Pad6)") (class "Default")
      (node (ref "DA5") (pin "6") (pintype "passive"))
      (node (ref "R114") (pin "1") (pintype "passive"))
      (node (ref "R117") (pin "1") (pintype "passive"))
    )
    (net (code "50") (name "Net-(DA5-Pad10)") (class "Default")
      (node (ref "DA5") (pin "10") (pintype "passive"))
      (node (ref "R100") (pin "1") (pintype "passive"))
      (node (ref "R107") (pin "2") (pintype "passive"))
    )
    (net (code "51") (name "Net-(DA5-Pad13)") (class "Default")
      (node (ref "DA5") (pin "13") (pintype "passive"))
      (node (ref "R47") (pin "1") (pintype "passive"))
      (node (ref "R48") (pin "2") (pintype "passive"))
    )
    (net (code "52") (name "Net-(DA5-Pad14)") (class "Default")
      (node (ref "DA5") (pin "14") (pintype "passive"))
      (node (ref "R47") (pin "2") (pintype "passive"))
      (node (ref "R49") (pin "2") (pintype "passive"))
    )
    (net (code "53") (name "Net-(DA6-Pad2)") (class "Default")
      (node (ref "DA6") (pin "2") (pintype "passive"))
      (node (ref "R65") (pin "2") (pintype "passive"))
      (node (ref "R67") (pin "1") (pintype "passive"))
    )
    (net (code "54") (name "Net-(DA6-Pad3)") (class "Default")
      (node (ref "DA6") (pin "3") (pintype "passive"))
      (node (ref "R64") (pin "1") (pintype "passive"))
      (node (ref "R69") (pin "1") (pintype "passive"))
    )
    (net (code "55") (name "Net-(DA6-Pad5)") (class "Default")
      (node (ref "DA6") (pin "5") (pintype "passive"))
      (node (ref "R59") (pin "1") (pintype "passive"))
      (node (ref "R66") (pin "1") (pintype "passive"))
    )
    (net (code "56") (name "Net-(DA6-Pad6)") (class "Default")
      (node (ref "DA6") (pin "6") (pintype "passive"))
      (node (ref "R58") (pin "1") (pintype "passive"))
      (node (ref "R60") (pin "1") (pintype "passive"))
    )
    (net (code "57") (name "Net-(DA7-Pad2)") (class "Default")
      (node (ref "DA7") (pin "2") (pintype "passive"))
      (node (ref "R77") (pin "1") (pintype "passive"))
      (node (ref "R86") (pin "2") (pintype "passive"))
    )
    (net (code "58") (name "Net-(DA7-Pad5)") (class "Default")
      (node (ref "DA7") (pin "5") (pintype "passive"))
      (node (ref "DA7") (pin "8") (pintype "passive"))
      (node (ref "R113") (pin "1") (pintype "passive"))
    )
    (net (code "59") (name "Net-(DA7-Pad6)") (class "Default")
      (node (ref "DA7") (pin "6") (pintype "passive"))
      (node (ref "R109") (pin "2") (pintype "passive"))
      (node (ref "R112") (pin "1") (pintype "passive"))
    )
    (net (code "60") (name "Net-(DA7-Pad10)") (class "Default")
      (node (ref "DA7") (pin "10") (pintype "passive"))
      (node (ref "DA7") (pin "12") (pintype "passive"))
      (node (ref "R87") (pin "2") (pintype "passive"))
      (node (ref "R88") (pin "1") (pintype "passive"))
    )
    (net (code "61") (name "Net-(DA7-Pad14)") (class "Default")
      (node (ref "DA7") (pin "14") (pintype "passive"))
      (node (ref "DA7") (pin "3") (pintype "passive"))
      (node (ref "R76") (pin "2") (pintype "passive"))
    )
    (net (code "62") (name "Net-(DA8-Pad1)") (class "Default")
      (node (ref "DA8") (pin "1") (pintype "passive"))
      (node (ref "DA8") (pin "2") (pintype "passive"))
      (node (ref "R98") (pin "1") (pintype "passive"))
    )
    (net (code "63") (name "Net-(DA8-Pad3)") (class "Default")
      (node (ref "DA8") (pin "3") (pintype "passive"))
      (node (ref "R101") (pin "1") (pintype "passive"))
      (node (ref "R103") (pin "1") (pintype "passive"))
    )
    (net (code "64") (name "Net-(DA8-Pad5)") (class "Default")
      (node (ref "DA8") (pin "5") (pintype "passive"))
      (node (ref "R104") (pin "3") (pintype "passive"))
    )
    (net (code "65") (name "Net-(DA8-Pad6)") (class "Default")
      (node (ref "DA8") (pin "6") (pintype "passive"))
      (node (ref "R106") (pin "2") (pintype "passive"))
      (node (ref "R98") (pin "2") (pintype "passive"))
    )
    (net (code "66") (name "Net-(DA8-Pad7)") (class "Default")
      (node (ref "DA8") (pin "7") (pintype "passive"))
      (node (ref "R106") (pin "1") (pintype "passive"))
      (node (ref "R111") (pin "1") (pintype "passive"))
    )
    (net (code "67") (name "Net-(DA10-K)") (class "Default")
      (node (ref "DA10") (pin "1") (pinfunction "K_1") (pintype "passive"))
      (node (ref "R139") (pin "2") (pintype "passive"))
      (node (ref "R140") (pin "2") (pintype "passive"))
    )
    (net (code "68") (name "Net-(DA18-Pad2)") (class "Default")
      (node (ref "DA18") (pin "2") (pintype "passive"))
      (node (ref "R212") (pin "2") (pintype "passive"))
      (node (ref "R214") (pin "1") (pintype "passive"))
    )
    (net (code "69") (name "Net-(DA18-Pad3)") (class "Default")
      (node (ref "DA18") (pin "3") (pintype "passive"))
      (node (ref "R211") (pin "2") (pintype "passive"))
      (node (ref "R213") (pin "1") (pintype "passive"))
    )
    (net (code "70") (name "Net-(M13-Pad3)") (class "Default")
      (node (ref "M13") (pin "3") (pintype "passive"))
      (node (ref "R213") (pin "2") (pintype "passive"))
    )
    (net (code "71") (name "Net-(M15-Pad3)") (class "Default")
      (node (ref "M15") (pin "3") (pintype "passive"))
      (node (ref "R69") (pin "2") (pintype "passive"))
    )
    (net (code "72") (name "Net-(M16-Pad3)") (class "Default")
      (node (ref "M16") (pin "3") (pintype "passive"))
      (node (ref "R66") (pin "2") (pintype "passive"))
    )
    (net (code "73") (name "Net-(M17-Pad1)") (class "Default")
      (node (ref "M17") (pin "1") (pintype "passive"))
      (node (ref "M18") (pin "3") (pintype "passive"))
      (node (ref "R92") (pin "1") (pintype "passive"))
    )
    (net (code "74") (name "Net-(Q2-B)") (class "Default")
      (node (ref "Q2") (pin "1") (pinfunction "B_1") (pintype "passive"))
      (node (ref "Q2") (pin "3") (pinfunction "C_3") (pintype "passive"))
      (node (ref "Q3") (pin "1") (pinfunction "B_1") (pintype "passive"))
      (node (ref "Q4") (pin "1") (pinfunction "B_1") (pintype "passive"))
      (node (ref "Q7") (pin "2") (pinfunction "E_2") (pintype "passive"))
    )
    (net (code "75") (name "Net-(Q2-E)") (class "Default")
      (node (ref "Q2") (pin "2") (pinfunction "E_2") (pintype "passive"))
      (node (ref "R62") (pin "2") (pintype "passive"))
    )
    (net (code "76") (name "Net-(Q3-C)") (class "Default")
      (node (ref "Q3") (pin "3") (pinfunction "C_3") (pintype "passive"))
      (node (ref "Q5") (pin "2") (pinfunction "E_2") (pintype "passive"))
    )
    (net (code "77") (name "Net-(Q3-E)") (class "Default")
      (node (ref "Q3") (pin "2") (pinfunction "E_2") (pintype "passive"))
      (node (ref "R56") (pin "2") (pintype "passive"))
    )
    (net (code "78") (name "Net-(Q4-C)") (class "Default")
      (node (ref "Q4") (pin "3") (pinfunction "C_3") (pintype "passive"))
      (node (ref "Q6") (pin "2") (pinfunction "E_2") (pintype "passive"))
    )
    (net (code "79") (name "Net-(Q4-E)") (class "Default")
      (node (ref "Q4") (pin "2") (pinfunction "E_2") (pintype "passive"))
      (node (ref "R57") (pin "2") (pintype "passive"))
    )
    (net (code "80") (name "Net-(Q5-B)") (class "Default")
      (node (ref "Q5") (pin "1") (pinfunction "B_1") (pintype "passive"))
      (node (ref "Q6") (pin "1") (pinfunction "B_1") (pintype "passive"))
      (node (ref "Q7") (pin "1") (pinfunction "B_1") (pintype "passive"))
      (node (ref "Q7") (pin "3") (pinfunction "C_3") (pintype "passive"))
      (node (ref "R68") (pin "1") (pintype "passive"))
    )
    (net (code "81") (name "Net-(Q5-C)") (class "Default")
      (node (ref "M2") (pin "1") (pintype "passive"))
      (node (ref "Q5") (pin "3") (pinfunction "C_3") (pintype "passive"))
      (node (ref "Q8") (pin "2") (pinfunction "E_2") (pintype "passive"))
      (node (ref "R45") (pin "2") (pintype "passive"))
    )
    (net (code "82") (name "Net-(Q6-C)") (class "Default")
      (node (ref "M4") (pin "1") (pintype "passive"))
      (node (ref "Q6") (pin "3") (pinfunction "C_3") (pintype "passive"))
      (node (ref "Q9") (pin "2") (pinfunction "E_2") (pintype "passive"))
      (node (ref "R54") (pin "2") (pintype "passive"))
    )
    (net (code "83") (name "Net-(Q10-B)") (class "Default")
      (node (ref "Q10") (pin "1") (pinfunction "B_1") (pintype "passive"))
      (node (ref "Q10") (pin "3") (pinfunction "C_3") (pintype "passive"))
      (node (ref "Q11") (pin "1") (pinfunction "B_1") (pintype "passive"))
      (node (ref "Q12") (pin "2") (pinfunction "E_2") (pintype "passive"))
    )
    (net (code "84") (name "Net-(Q10-E)") (class "Default")
      (node (ref "Q10") (pin "2") (pinfunction "E_2") (pintype "passive"))
      (node (ref "R72") (pin "2") (pintype "passive"))
    )
    (net (code "85") (name "Net-(Q11-C)") (class "Default")
      (node (ref "Q11") (pin "3") (pinfunction "C_3") (pintype "passive"))
      (node (ref "Q13") (pin "2") (pinfunction "E_2") (pintype "passive"))
    )
    (net (code "86") (name "Net-(Q11-E)") (class "Default")
      (node (ref "Q11") (pin "2") (pinfunction "E_2") (pintype "passive"))
      (node (ref "R73") (pin "2") (pintype "passive"))
    )
    (net (code "87") (name "Net-(Q12-B)") (class "Default")
      (node (ref "Q12") (pin "1") (pinfunction "B_1") (pintype "passive"))
      (node (ref "Q12") (pin "3") (pinfunction "C_3") (pintype "passive"))
      (node (ref "Q13") (pin "1") (pinfunction "B_1") (pintype "passive"))
      (node (ref "R85") (pin "1") (pintype "passive"))
    )
    (net (code "88") (name "Net-(Q13-C)") (class "Default")
      (node (ref "M10") (pin "1") (pintype "passive"))
      (node (ref "Q13") (pin "3") (pinfunction "C_3") (pintype "passive"))
      (node (ref "Q14") (pin "2") (pinfunction "E_2") (pintype "passive"))
    )
    (net (code "89") (name "Net-(Q14-C)") (class "Default")
      (node (ref "Q14") (pin "3") (pinfunction "C_3") (pintype "passive"))
      (node (ref "R210") (pin "1") (pintype "passive"))
    )
    (net (code "90") (name "Net-(R78-Pad2)") (class "Default")
      (node (ref "R78") (pin "2") (pintype "passive"))
      (node (ref "R86") (pin "1") (pintype "passive"))
    )
    (net (code "91") (name "Net-(R109-Pad1)") (class "Default")
      (node (ref "R109") (pin "1") (pintype "passive"))
      (node (ref "R89") (pin "1") (pintype "passive"))
    )
  )
)
